# A5000_8MB_Glue.net
KiCad netlist of a schematic drawn in Altium Designer
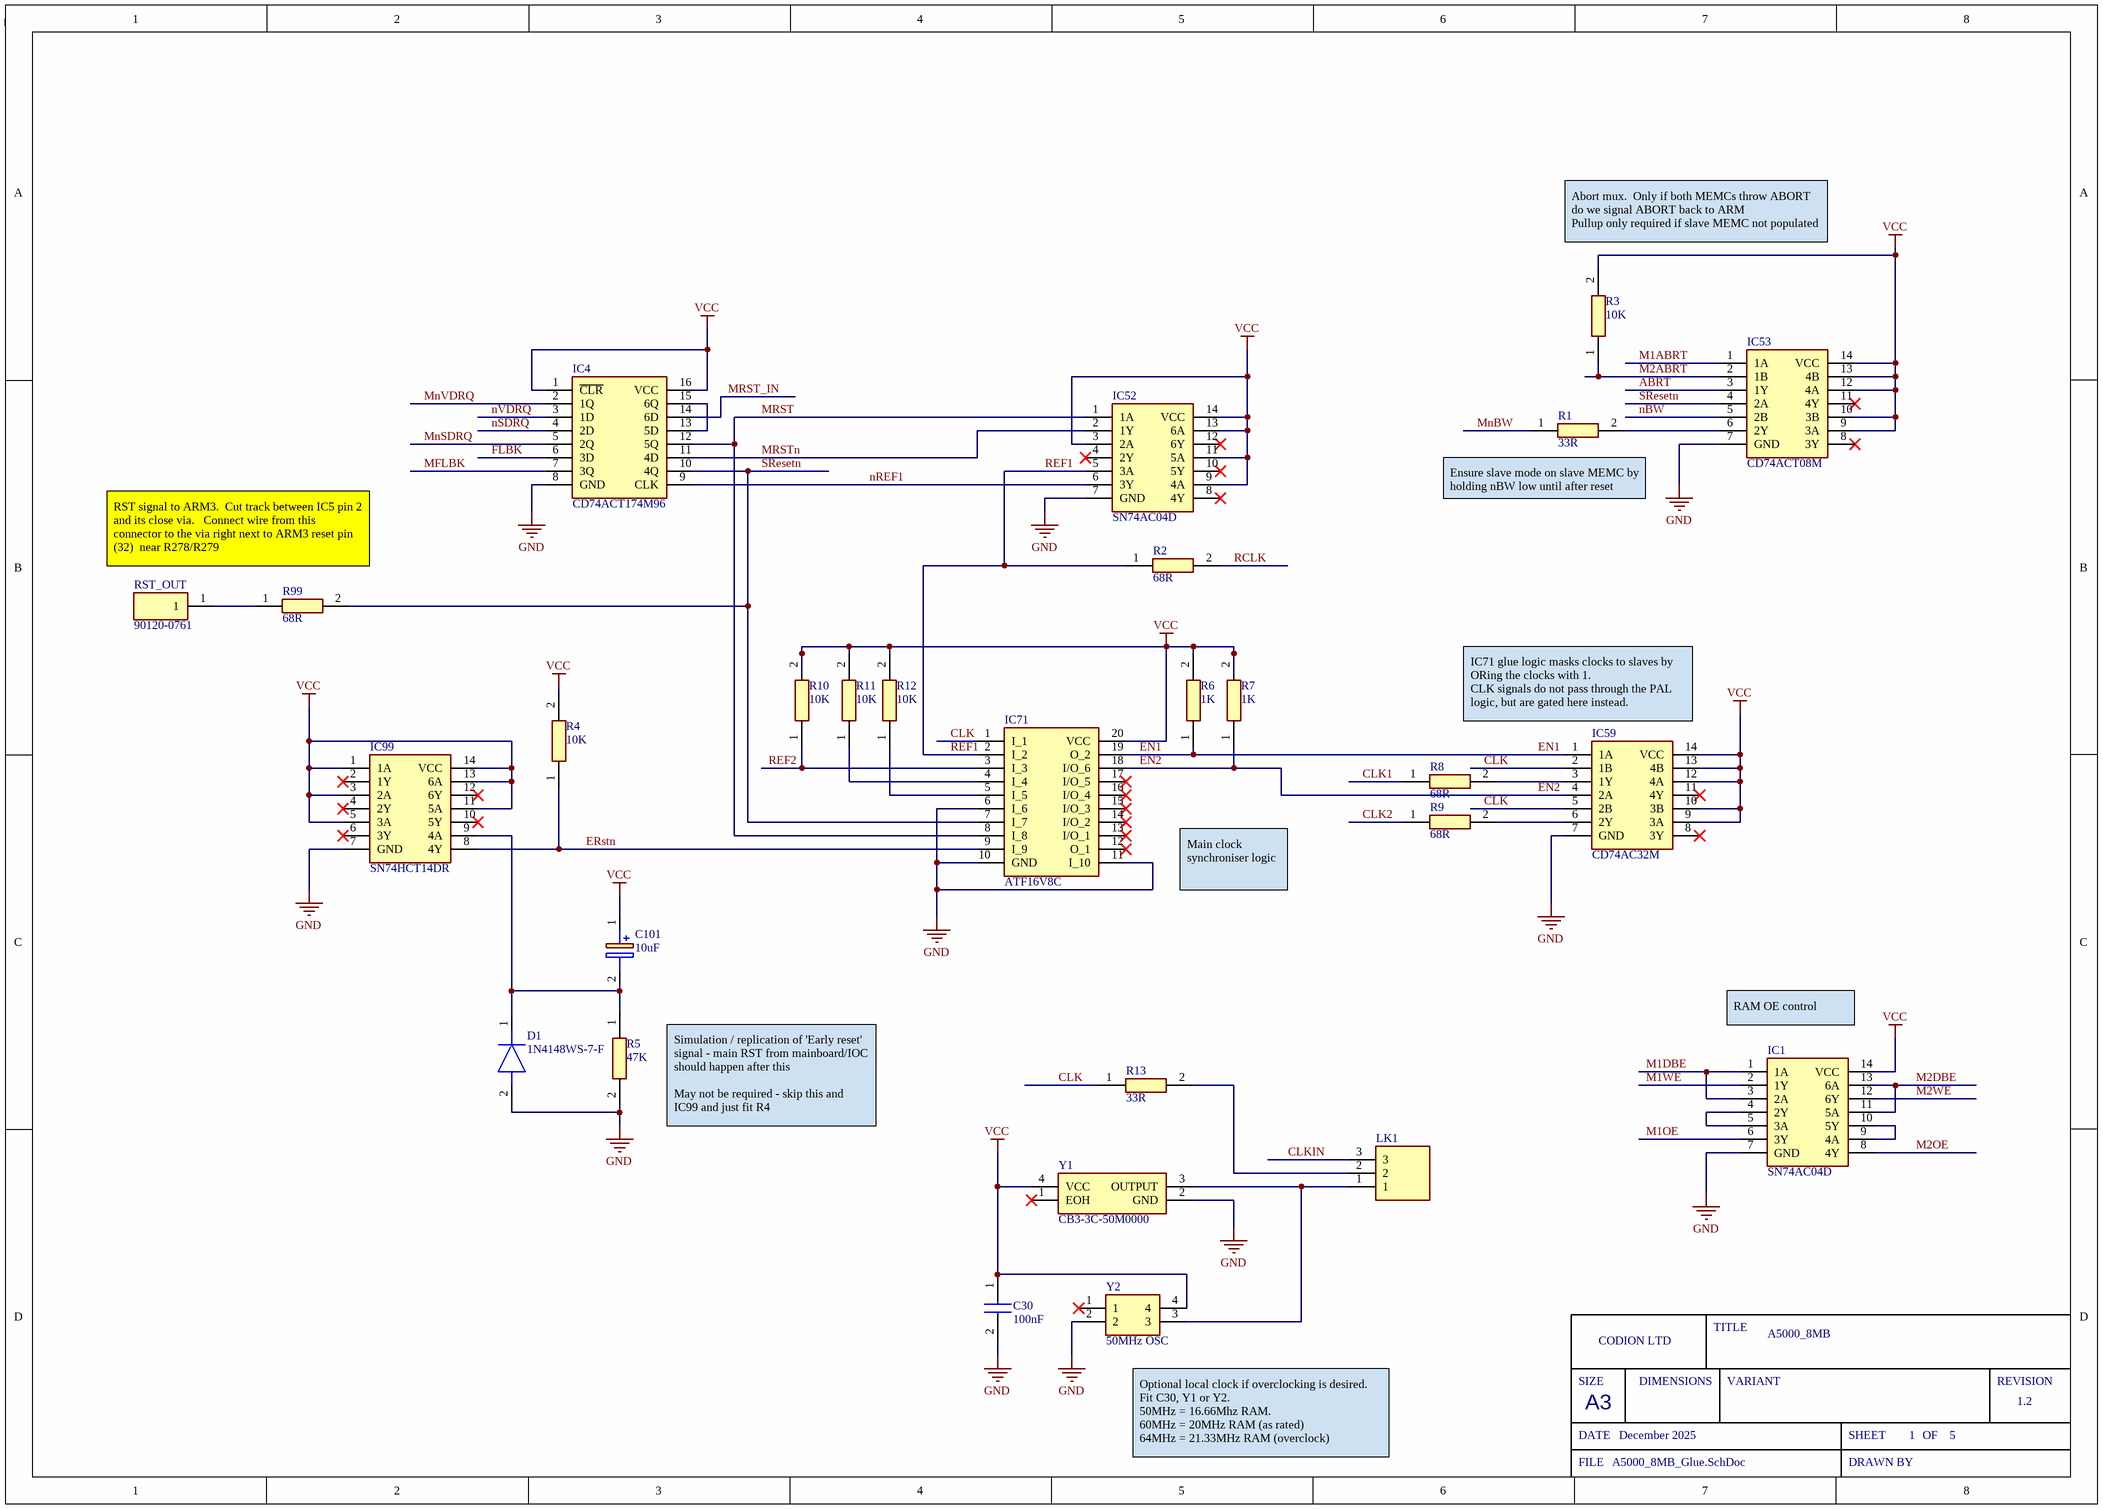
[diagram p0: A5000_8MB_Glue.SchDoc]

(export (version "E")
  (design (tool "Eeschema 10.0.6"))
  (components
    (comp (ref "C30")
      (value "100nF")
      (footprint "0805cap")
      (description "Capacitor")
      (fields
        (field (name "MANUFACTURER_PART_NUMBER") "C2012X7R1H104K125AM")
        (field (name "MOUSER PART NUMBER") "810-C2012X7R1H104KT5")
      )
      (libsource (lib "Acorn") (part "100nF0805"))
    )
    (comp (ref "C101")
      (value "10uF")
      (footprint "SamacSys:EEE0GA101SR")
      (description "Capacitor Polarised")
      (fields
        (field (name "MANUFACTURER_PART_NUMBER") "EEE-1EA100SR")
        (field (name "MOUSER PART NUMBER") "667-EEE-1EA100SR")
      )
      (libsource (lib "*") (part "EEE-1EA100SR"))
    )
    (comp (ref "D1")
      (value "1N4148WS-7-F")
      (footprint "SamacSys:SOD2513X120N")
      (description "Diode")
      (fields (field (name "MOUSER PART NUMBER") "621-1N4148WS-F") (field (name "LCSC PART #") "C2128"))
      (libsource (lib "SamacSys") (part "1N4148WS-7-F"))
    )
    (comp (ref "IC1")
      (value "SN74AC04D")
      (footprint "SamacSys:SOIC127P600X175-14N")
      (description "Integrated Circuit")
      (fields (field (name "MOUSER PART NUMBER") "595-SN74AC04D") (field (name "LCSC PART #") "C352940"))
      (libsource (lib "SamacSys") (part "SN74AC04D"))
    )
    (comp (ref "IC4")
      (value "CD74ACT174M96")
      (footprint "SamacSys:SOIC127P600X175-16N")
      (description "Integrated Circuit")
      (fields (field (name "MOUSER PART NUMBER") "595-CD74ACT174M96"))
      (libsource (lib "*") (part "CD74ACT174M96"))
    )
    (comp (ref "IC52")
      (value "SN74AC04D")
      (footprint "SamacSys:SOIC127P600X175-14N")
      (description "Integrated Circuit")
      (fields (field (name "MOUSER PART NUMBER") "595-SN74AC04D") (field (name "LCSC PART #") "C352940"))
      (libsource (lib "SamacSys") (part "SN74AC04D"))
    )
    (comp (ref "IC53")
      (value "CD74ACT08M")
      (footprint "SamacSys:SOIC127P600X175-14N")
      (description "Integrated Circuit")
      (fields (field (name "MOUSER PART NUMBER") "595-CD74ACT08M") (field (name "LCSC PART #") "C233452"))
      (libsource (lib "*") (part "CD74ACT08M"))
    )
    (comp (ref "IC59")
      (value "CD74AC32M")
      (footprint "SamacSys:SOIC127P600X175-14N")
      (description "Integrated Circuit")
      (fields (field (name "MOUSER PART NUMBER") "595-CD74AC32M") (field (name "LCSC PART #") "C352943"))
      (libsource (lib "SamacSys") (part "CD74AC32M"))
    )
    (comp (ref "IC71")
      (value "ATF16V8C")
      (footprint "SamacSys:DIP762W66P254L2692H508Q20N")
      (description "Integrated Circuit")
      (fields
        (field (name "MANUFACTURER_PART_NUMBER") "PAL16R4AMJ")
        (field (name "MOUSER PART NUMBER") "595-PAL16R4AMJ")
      )
      (libsource (lib "*") (part "PAL16R4AMJ"))
    )
    (comp (ref "IC99")
      (value "SN74HCT14DR")
      (footprint "SamacSys:SOIC127P600X175-14N")
      (description "Integrated Circuit")
      (fields (field (name "MOUSER PART NUMBER") "595-SN74HCT14DR") (field (name "LCSC PART #") "C6769"))
      (libsource (lib "SamacSys") (part "SN74HCT14DR"))
    )
    (comp (ref "LK1")
      (value "PREC003SAAN-RC")
      (footprint "SamacSys:HDRV3W64P0X254_1X3_762X254X868P")
      (description "Connector")
      (libsource (lib "SamacSys") (part "PREC003SAAN-RC"))
    )
    (comp (ref "R1")
      (value "33R")
      (footprint "SamacSys:RESC1005X40N")
      (description "Resistor")
      (fields
        (field (name "MANUFACTURER_PART_NUMBER") "CRCW040233R0FKED")
        (field (name "MOUSER PART NUMBER") "71-CRCW0402-33-E3")
      )
      (libsource (lib "SamacSys") (part "CRCW040233R0FKED"))
    )
    (comp (ref "R2")
      (value "68R")
      (footprint "SamacSys:RESC1005X40N")
      (description "Resistor")
      (fields
        (field (name "MANUFACTURER_PART_NUMBER") "CRCW040268R0FKEDHP")
        (field (name "MOUSER PART NUMBER") "71-CRCW040268R0FKEDH")
      )
      (libsource (lib "SamacSys") (part "CRCW040268R0FKEDHP"))
    )
    (comp (ref "R3")
      (value "10K")
      (footprint "SamacSys:RESC1005X40N")
      (description "Resistor")
      (fields
        (field (name "MANUFACTURER_PART_NUMBER") "CRCW040210K0FKEDHP")
        (field (name "MOUSER PART NUMBER") "71-CRCW040210K0FKEDH")
      )
      (libsource (lib "SamacSys") (part "CRCW040210K0FKEDHP"))
    )
    (comp (ref "R4")
      (value "10K")
      (footprint "SamacSys:RESC1005X40N")
      (description "Resistor")
      (fields
        (field (name "MANUFACTURER_PART_NUMBER") "CRCW040210K0FKEDHP")
        (field (name "MOUSER PART NUMBER") "71-CRCW040210K0FKEDH")
      )
      (libsource (lib "SamacSys") (part "CRCW040210K0FKEDHP"))
    )
    (comp (ref "R5")
      (value "47K")
      (footprint "SamacSys:RESC1005X40N")
      (description "Resistor")
      (fields
        (field (name "MANUFACTURER_PART_NUMBER") "CRCW040247K0FKED")
        (field (name "MOUSER PART NUMBER") "71-CRCW0402-47K-E3")
      )
      (libsource (lib "SamacSys") (part "CRCW040247K0FKED"))
    )
    (comp (ref "R6")
      (value "1K")
      (footprint "SamacSys:RESC1005X40N")
      (description "Resistor")
      (fields
        (field (name "MANUFACTURER_PART_NUMBER") "CRCW04021K00JNED")
        (field (name "MOUSER PART NUMBER") "71-CRCW0402J-1.0K-E3")
      )
      (libsource (lib "SamacSys") (part "CRCW04021K00JNED"))
    )
    (comp (ref "R7")
      (value "1K")
      (footprint "SamacSys:RESC1005X40N")
      (description "Resistor")
      (fields
        (field (name "MANUFACTURER_PART_NUMBER") "CRCW04021K00JNED")
        (field (name "MOUSER PART NUMBER") "71-CRCW0402J-1.0K-E3")
      )
      (libsource (lib "SamacSys") (part "CRCW04021K00JNED"))
    )
    (comp (ref "R8")
      (value "68R")
      (footprint "SamacSys:RESC1005X40N")
      (description "Resistor")
      (fields
        (field (name "MANUFACTURER_PART_NUMBER") "CRCW040268R0FKEDHP")
        (field (name "MOUSER PART NUMBER") "71-CRCW040268R0FKEDH")
      )
      (libsource (lib "SamacSys") (part "CRCW040268R0FKEDHP"))
    )
    (comp (ref "R9")
      (value "68R")
      (footprint "SamacSys:RESC1005X40N")
      (description "Resistor")
      (fields
        (field (name "MANUFACTURER_PART_NUMBER") "CRCW040268R0FKEDHP")
        (field (name "MOUSER PART NUMBER") "71-CRCW040268R0FKEDH")
      )
      (libsource (lib "SamacSys") (part "CRCW040268R0FKEDHP"))
    )
    (comp (ref "R10")
      (value "10K")
      (footprint "SamacSys:RESC1005X40N")
      (description "Resistor")
      (fields
        (field (name "MANUFACTURER_PART_NUMBER") "CRCW040210K0FKEDHP")
        (field (name "MOUSER PART NUMBER") "71-CRCW040210K0FKEDH")
      )
      (libsource (lib "SamacSys") (part "CRCW040210K0FKEDHP"))
    )
    (comp (ref "R11")
      (value "10K")
      (footprint "SamacSys:RESC1005X40N")
      (description "Resistor")
      (fields
        (field (name "MANUFACTURER_PART_NUMBER") "CRCW040210K0FKEDHP")
        (field (name "MOUSER PART NUMBER") "71-CRCW040210K0FKEDH")
      )
      (libsource (lib "SamacSys") (part "CRCW040210K0FKEDHP"))
    )
    (comp (ref "R12")
      (value "10K")
      (footprint "SamacSys:RESC1005X40N")
      (description "Resistor")
      (fields
        (field (name "MANUFACTURER_PART_NUMBER") "CRCW040210K0FKEDHP")
        (field (name "MOUSER PART NUMBER") "71-CRCW040210K0FKEDH")
      )
      (libsource (lib "SamacSys") (part "CRCW040210K0FKEDHP"))
    )
    (comp (ref "R13")
      (value "33R")
      (footprint "SamacSys:RESC1005X40N")
      (description "Resistor")
      (fields
        (field (name "MANUFACTURER_PART_NUMBER") "CRCW040233R0FKED")
        (field (name "MOUSER PART NUMBER") "71-CRCW0402-33-E3")
      )
      (libsource (lib "SamacSys") (part "CRCW040233R0FKED"))
    )
    (comp (ref "R99")
      (value "68R")
      (footprint "SamacSys:RESC1005X40N")
      (description "Resistor")
      (fields
        (field (name "MANUFACTURER_PART_NUMBER") "CRCW040268R0FKEDHP")
        (field (name "MOUSER PART NUMBER") "71-CRCW040268R0FKEDH")
      )
      (libsource (lib "SamacSys") (part "CRCW040268R0FKEDHP"))
    )
    (comp (ref "RST_OUT")
      (value "90120-0761")
      (footprint "SamacSys:HDRV1W90P0X254_1X1_232X249X560P")
      (description "Connector")
      (fields (field (name "MOUSER PART NUMBER") "538-90120-0761"))
      (libsource (lib "SamacSys") (part "90120-0761"))
    )
    (comp (ref "Y1")
      (value "CB3-3C-50M0000")
      (footprint "SamacSys:CB33C50M0000")
      (description "Crystal or Oscillator")
      (fields (field (name "MOUSER PART NUMBER") "774-CB3-3C-50M0"))
      (libsource (lib "*") (part "CB3-3C-50M0000"))
    )
    (comp (ref "Y2")
      (value "50MHz OSC")
      (footprint "SamacSys:DIPS762W56P1524L1778H241Q4N")
      (fields
        (field (name "MANUFACTURER_PART_NUMBER") "1107741")
        (field (name "MOUSER PART NUMBER") "535-1107741")
      )
      (libsource (lib "*") (part "1107741"))
    )
  )
  (nets
    (net (code "1") (name "/ABRT") (class "Default")
      (node (ref "IC53") (pin "3") (pinfunction "1Y_3") (pintype "passive"))
    )
    (net (code "2") (name "/CLK") (class "Default")
      (node (ref "IC59") (pin "2") (pinfunction "1B_2") (pintype "passive"))
      (node (ref "IC59") (pin "5") (pinfunction "2B_5") (pintype "passive"))
      (node (ref "IC71") (pin "1") (pinfunction "I_1_1") (pintype "passive"))
      (node (ref "R13") (pin "1") (pinfunction "1_1") (pintype "passive"))
    )
    (net (code "3") (name "/CLK1") (class "Default")
      (node (ref "R8") (pin "1") (pinfunction "1_1") (pintype "passive"))
    )
    (net (code "4") (name "/CLK2") (class "Default")
      (node (ref "R9") (pin "1") (pinfunction "1_1") (pintype "passive"))
    )
    (net (code "5") (name "/CLKIN") (class "Default")
      (node (ref "LK1") (pin "3") (pinfunction "3_3") (pintype "passive"))
    )
    (net (code "6") (name "/EN1") (class "Default")
      (node (ref "IC59") (pin "1") (pinfunction "1A_1") (pintype "passive"))
      (node (ref "IC71") (pin "19") (pinfunction "O_2_19") (pintype "passive"))
      (node (ref "R6") (pin "1") (pinfunction "1_1") (pintype "passive"))
    )
    (net (code "7") (name "/EN2") (class "Default")
      (node (ref "IC59") (pin "4") (pinfunction "2A_4") (pintype "passive"))
      (node (ref "IC71") (pin "18") (pinfunction "I/O_6_18") (pintype "passive"))
      (node (ref "R7") (pin "1") (pinfunction "1_1") (pintype "passive"))
    )
    (net (code "8") (name "/ERstn") (class "Default")
      (node (ref "IC71") (pin "9") (pinfunction "I_9_9") (pintype "passive"))
      (node (ref "IC99") (pin "8") (pinfunction "4Y_8") (pintype "passive"))
      (node (ref "R4") (pin "1") (pinfunction "1_1") (pintype "passive"))
    )
    (net (code "9") (name "/FLBK") (class "Default")
      (node (ref "IC4") (pin "6") (pinfunction "3D_6") (pintype "passive"))
    )
    (net (code "10") (name "/M1ABRT") (class "Default")
      (node (ref "IC53") (pin "1") (pinfunction "1A_1") (pintype "passive"))
    )
    (net (code "11") (name "/M1DBE") (class "Default")
      (node (ref "IC1") (pin "1") (pinfunction "1A_1") (pintype "passive"))
      (node (ref "IC1") (pin "3") (pinfunction "2A_3") (pintype "passive"))
    )
    (net (code "12") (name "/M1OE") (class "Default")
      (node (ref "IC1") (pin "6") (pinfunction "3Y_6") (pintype "passive"))
    )
    (net (code "13") (name "/M1WE") (class "Default")
      (node (ref "IC1") (pin "2") (pinfunction "1Y_2") (pintype "passive"))
    )
    (net (code "14") (name "/M2ABRT") (class "Default")
      (node (ref "IC53") (pin "2") (pinfunction "1B_2") (pintype "passive"))
      (node (ref "R3") (pin "1") (pinfunction "1_1") (pintype "passive"))
    )
    (net (code "15") (name "/M2DBE") (class "Default")
      (node (ref "IC1") (pin "11") (pinfunction "5A_11") (pintype "passive"))
      (node (ref "IC1") (pin "13") (pinfunction "6A_13") (pintype "passive"))
    )
    (net (code "16") (name "/M2OE") (class "Default")
      (node (ref "IC1") (pin "8") (pinfunction "4Y_8") (pintype "passive"))
    )
    (net (code "17") (name "/M2WE") (class "Default")
      (node (ref "IC1") (pin "12") (pinfunction "6Y_12") (pintype "passive"))
    )
    (net (code "18") (name "/MFLBK") (class "Default")
      (node (ref "IC4") (pin "7") (pinfunction "3Q_7") (pintype "passive"))
    )
    (net (code "19") (name "/MRST") (class "Default")
      (node (ref "IC4") (pin "12") (pinfunction "5Q_12") (pintype "passive"))
      (node (ref "IC52") (pin "1") (pinfunction "1A_1") (pintype "passive"))
      (node (ref "IC71") (pin "8") (pinfunction "I_8_8") (pintype "passive"))
    )
    (net (code "20") (name "/MRST_IN") (class "Default")
      (node (ref "IC4") (pin "14") (pinfunction "6D_14") (pintype "passive"))
    )
    (net (code "21") (name "/MRSTn") (class "Default")
      (node (ref "IC4") (pin "11") (pinfunction "4D_11") (pintype "passive"))
      (node (ref "IC52") (pin "2") (pinfunction "1Y_2") (pintype "passive"))
    )
    (net (code "22") (name "/MnBW") (class "Default")
      (node (ref "R1") (pin "1") (pinfunction "1_1") (pintype "passive"))
    )
    (net (code "23") (name "/MnSDRQ") (class "Default")
      (node (ref "IC4") (pin "5") (pinfunction "2Q_5") (pintype "passive"))
    )
    (net (code "24") (name "/MnVDRQ") (class "Default")
      (node (ref "IC4") (pin "2") (pinfunction "1Q_2") (pintype "passive"))
    )
    (net (code "25") (name "/RCLK") (class "Default")
      (node (ref "R2") (pin "2") (pinfunction "2_2") (pintype "passive"))
    )
    (net (code "26") (name "/REF1") (class "Default")
      (node (ref "IC52") (pin "5") (pinfunction "3A_5") (pintype "passive"))
      (node (ref "IC71") (pin "2") (pinfunction "I_2_2") (pintype "passive"))
      (node (ref "R2") (pin "1") (pinfunction "1_1") (pintype "passive"))
    )
    (net (code "27") (name "/REF2") (class "Default")
      (node (ref "IC71") (pin "3") (pinfunction "I_3_3") (pintype "passive"))
      (node (ref "R10") (pin "1") (pinfunction "1_1") (pintype "passive"))
    )
    (net (code "28") (name "/SResetn") (class "Default")
      (node (ref "IC4") (pin "10") (pinfunction "4Q_10") (pintype "passive"))
      (node (ref "IC53") (pin "4") (pinfunction "2A_4") (pintype "passive"))
      (node (ref "IC71") (pin "7") (pinfunction "I_7_7") (pintype "passive"))
      (node (ref "R99") (pin "2") (pinfunction "2_2") (pintype "passive"))
    )
    (net (code "29") (name "/nBW") (class "Default")
      (node (ref "IC53") (pin "5") (pinfunction "2B_5") (pintype "passive"))
    )
    (net (code "30") (name "/nREF1") (class "Default")
      (node (ref "IC4") (pin "9") (pinfunction "CLK_9") (pintype "passive"))
      (node (ref "IC52") (pin "6") (pinfunction "3Y_6") (pintype "passive"))
    )
    (net (code "31") (name "/nSDRQ") (class "Default")
      (node (ref "IC4") (pin "4") (pinfunction "2D_4") (pintype "passive"))
    )
    (net (code "32") (name "/nVDRQ") (class "Default")
      (node (ref "IC4") (pin "3") (pinfunction "1D_3") (pintype "passive"))
    )
    (net (code "33") (name "GND") (class "Default")
      (node (ref "C30") (pin "2") (pinfunction "2_2") (pintype "passive"))
      (node (ref "D1") (pin "2") (pinfunction "A_2") (pintype "passive"))
      (node (ref "IC1") (pin "7") (pinfunction "GND_7") (pintype "passive"))
      (node (ref "IC4") (pin "8") (pinfunction "GND_8") (pintype "passive"))
      (node (ref "IC52") (pin "7") (pinfunction "GND_7") (pintype "passive"))
      (node (ref "IC53") (pin "7") (pinfunction "GND_7") (pintype "passive"))
      (node (ref "IC59") (pin "7") (pinfunction "GND_7") (pintype "passive"))
      (node (ref "IC71") (pin "10") (pinfunction "GND_10") (pintype "passive"))
      (node (ref "IC71") (pin "11") (pinfunction "I_10_11") (pintype "passive"))
      (node (ref "IC71") (pin "6") (pinfunction "I_6_6") (pintype "passive"))
      (node (ref "IC99") (pin "7") (pinfunction "GND_7") (pintype "passive"))
      (node (ref "R5") (pin "2") (pinfunction "2_2") (pintype "passive"))
      (node (ref "Y1") (pin "2") (pinfunction "GND_2") (pintype "passive"))
      (node (ref "Y2") (pin "2") (pinfunction "2_2") (pintype "passive"))
    )
    (net (code "34") (name "Net-(C101--)") (class "Default")
      (node (ref "C101") (pin "2") (pinfunction "-_2") (pintype "passive"))
      (node (ref "D1") (pin "1") (pinfunction "K_1") (pintype "passive"))
      (node (ref "IC99") (pin "9") (pinfunction "4A_9") (pintype "passive"))
      (node (ref "R5") (pin "1") (pinfunction "1_1") (pintype "passive"))
    )
    (net (code "35") (name "Net-(IC1-2Y)") (class "Default")
      (node (ref "IC1") (pin "4") (pinfunction "2Y_4") (pintype "passive"))
      (node (ref "IC1") (pin "5") (pinfunction "3A_5") (pintype "passive"))
    )
    (net (code "36") (name "Net-(IC1-4A)") (class "Default")
      (node (ref "IC1") (pin "10") (pinfunction "5Y_10") (pintype "passive"))
      (node (ref "IC1") (pin "9") (pinfunction "4A_9") (pintype "passive"))
    )
    (net (code "37") (name "Net-(IC4-5D)") (class "Default")
      (node (ref "IC4") (pin "13") (pinfunction "5D_13") (pintype "passive"))
      (node (ref "IC4") (pin "15") (pinfunction "6Q_15") (pintype "passive"))
    )
    (net (code "38") (name "Net-(IC53-2Y)") (class "Default")
      (node (ref "IC53") (pin "6") (pinfunction "2Y_6") (pintype "passive"))
      (node (ref "R1") (pin "2") (pinfunction "2_2") (pintype "passive"))
    )
    (net (code "39") (name "Net-(IC59-1Y)") (class "Default")
      (node (ref "IC59") (pin "3") (pinfunction "1Y_3") (pintype "passive"))
      (node (ref "R8") (pin "2") (pinfunction "2_2") (pintype "passive"))
    )
    (net (code "40") (name "Net-(IC59-2Y)") (class "Default")
      (node (ref "IC59") (pin "6") (pinfunction "2Y_6") (pintype "passive"))
      (node (ref "R9") (pin "2") (pinfunction "2_2") (pintype "passive"))
    )
    (net (code "41") (name "Net-(IC71-I_4)") (class "Default")
      (node (ref "IC71") (pin "4") (pinfunction "I_4_4") (pintype "passive"))
      (node (ref "R11") (pin "1") (pinfunction "1_1") (pintype "passive"))
    )
    (net (code "42") (name "Net-(IC71-I_5)") (class "Default")
      (node (ref "IC71") (pin "5") (pinfunction "I_5_5") (pintype "passive"))
      (node (ref "R12") (pin "1") (pinfunction "1_1") (pintype "passive"))
    )
    (net (code "43") (name "Net-(LK1-Pad2)") (class "Default")
      (node (ref "LK1") (pin "2") (pinfunction "2_2") (pintype "passive"))
      (node (ref "R13") (pin "2") (pinfunction "2_2") (pintype "passive"))
    )
    (net (code "44") (name "Net-(R99-Pad1)") (class "Default")
      (node (ref "R99") (pin "1") (pinfunction "1_1") (pintype "passive"))
      (node (ref "RST_OUT") (pin "1") (pinfunction "1_1") (pintype "passive"))
    )
    (net (code "45") (name "Net-(Y1-OUTPUT)") (class "Default")
      (node (ref "LK1") (pin "1") (pinfunction "1_1") (pintype "passive"))
      (node (ref "Y1") (pin "3") (pinfunction "OUTPUT_3") (pintype "passive"))
      (node (ref "Y2") (pin "3") (pinfunction "3_3") (pintype "passive"))
    )
    (net (code "46") (name "VCC") (class "Default")
      (node (ref "C101") (pin "1") (pinfunction "+_1") (pintype "passive"))
      (node (ref "C30") (pin "1") (pinfunction "1_1") (pintype "passive"))
      (node (ref "IC1") (pin "14") (pinfunction "VCC_14") (pintype "passive"))
      (node (ref "IC4") (pin "1") (pinfunction "~{CLR}_1") (pintype "passive"))
      (node (ref "IC4") (pin "16") (pinfunction "VCC_16") (pintype "passive"))
      (node (ref "IC52") (pin "11") (pinfunction "5A_11") (pintype "passive"))
      (node (ref "IC52") (pin "13") (pinfunction "6A_13") (pintype "passive"))
      (node (ref "IC52") (pin "14") (pinfunction "VCC_14") (pintype "passive"))
      (node (ref "IC52") (pin "3") (pinfunction "2A_3") (pintype "passive"))
      (node (ref "IC52") (pin "9") (pinfunction "4A_9") (pintype "passive"))
      (node (ref "IC53") (pin "10") (pinfunction "3B_10") (pintype "passive"))
      (node (ref "IC53") (pin "12") (pinfunction "4A_12") (pintype "passive"))
      (node (ref "IC53") (pin "13") (pinfunction "4B_13") (pintype "passive"))
      (node (ref "IC53") (pin "14") (pinfunction "VCC_14") (pintype "passive"))
      (node (ref "IC53") (pin "9") (pinfunction "3A_9") (pintype "passive"))
      (node (ref "IC59") (pin "10") (pinfunction "3B_10") (pintype "passive"))
      (node (ref "IC59") (pin "12") (pinfunction "4A_12") (pintype "passive"))
      (node (ref "IC59") (pin "13") (pinfunction "4B_13") (pintype "passive"))
      (node (ref "IC59") (pin "14") (pinfunction "VCC_14") (pintype "passive"))
      (node (ref "IC59") (pin "9") (pinfunction "3A_9") (pintype "passive"))
      (node (ref "IC71") (pin "20") (pinfunction "VCC_20") (pintype "passive"))
      (node (ref "IC99") (pin "1") (pinfunction "1A_1") (pintype "passive"))
      (node (ref "IC99") (pin "11") (pinfunction "5A_11") (pintype "passive"))
      (node (ref "IC99") (pin "13") (pinfunction "6A_13") (pintype "passive"))
      (node (ref "IC99") (pin "14") (pinfunction "VCC_14") (pintype "passive"))
      (node (ref "IC99") (pin "3") (pinfunction "2A_3") (pintype "passive"))
      (node (ref "IC99") (pin "5") (pinfunction "3A_5") (pintype "passive"))
      (node (ref "R10") (pin "2") (pinfunction "2_2") (pintype "passive"))
      (node (ref "R11") (pin "2") (pinfunction "2_2") (pintype "passive"))
      (node (ref "R12") (pin "2") (pinfunction "2_2") (pintype "passive"))
      (node (ref "R3") (pin "2") (pinfunction "2_2") (pintype "passive"))
      (node (ref "R4") (pin "2") (pinfunction "2_2") (pintype "passive"))
      (node (ref "R6") (pin "2") (pinfunction "2_2") (pintype "passive"))
      (node (ref "R7") (pin "2") (pinfunction "2_2") (pintype "passive"))
      (node (ref "Y1") (pin "4") (pinfunction "VCC_4") (pintype "passive"))
      (node (ref "Y2") (pin "4") (pinfunction "4_4") (pintype "passive"))
    )
    (net (code "47") (name "unconnected-(IC52-2Y-Pad4)") (class "Default")
      (node (ref "IC52") (pin "4") (pinfunction "2Y_4") (pintype "passive+no_connect"))
    )
    (net (code "48") (name "unconnected-(IC52-4Y-Pad8)") (class "Default")
      (node (ref "IC52") (pin "8") (pinfunction "4Y_8") (pintype "passive+no_connect"))
    )
    (net (code "49") (name "unconnected-(IC52-5Y-Pad10)") (class "Default")
      (node (ref "IC52") (pin "10") (pinfunction "5Y_10") (pintype "passive+no_connect"))
    )
    (net (code "50") (name "unconnected-(IC52-6Y-Pad12)") (class "Default")
      (node (ref "IC52") (pin "12") (pinfunction "6Y_12") (pintype "passive+no_connect"))
    )
    (net (code "51") (name "unconnected-(IC53-3Y-Pad8)") (class "Default")
      (node (ref "IC53") (pin "8") (pinfunction "3Y_8") (pintype "passive+no_connect"))
    )
    (net (code "52") (name "unconnected-(IC53-4Y-Pad11)") (class "Default")
      (node (ref "IC53") (pin "11") (pinfunction "4Y_11") (pintype "passive+no_connect"))
    )
    (net (code "53") (name "unconnected-(IC59-3Y-Pad8)") (class "Default")
      (node (ref "IC59") (pin "8") (pinfunction "3Y_8") (pintype "passive+no_connect"))
    )
    (net (code "54") (name "unconnected-(IC59-4Y-Pad11)") (class "Default")
      (node (ref "IC59") (pin "11") (pinfunction "4Y_11") (pintype "passive+no_connect"))
    )
    (net (code "55") (name "unconnected-(IC71-I{slash}O_1-Pad13)") (class "Default")
      (node (ref "IC71") (pin "13") (pinfunction "I/O_1_13") (pintype "passive+no_connect"))
    )
    (net (code "56") (name "unconnected-(IC71-I{slash}O_2-Pad14)") (class "Default")
      (node (ref "IC71") (pin "14") (pinfunction "I/O_2_14") (pintype "passive+no_connect"))
    )
    (net (code "57") (name "unconnected-(IC71-I{slash}O_3-Pad15)") (class "Default")
      (node (ref "IC71") (pin "15") (pinfunction "I/O_3_15") (pintype "passive+no_connect"))
    )
    (net (code "58") (name "unconnected-(IC71-I{slash}O_4-Pad16)") (class "Default")
      (node (ref "IC71") (pin "16") (pinfunction "I/O_4_16") (pintype "passive+no_connect"))
    )
    (net (code "59") (name "unconnected-(IC71-I{slash}O_5-Pad17)") (class "Default")
      (node (ref "IC71") (pin "17") (pinfunction "I/O_5_17") (pintype "passive+no_connect"))
    )
    (net (code "60") (name "unconnected-(IC71-O_1-Pad12)") (class "Default")
      (node (ref "IC71") (pin "12") (pinfunction "O_1_12") (pintype "passive+no_connect"))
    )
    (net (code "61") (name "unconnected-(IC99-1Y-Pad2)") (class "Default")
      (node (ref "IC99") (pin "2") (pinfunction "1Y_2") (pintype "passive+no_connect"))
    )
    (net (code "62") (name "unconnected-(IC99-2Y-Pad4)") (class "Default")
      (node (ref "IC99") (pin "4") (pinfunction "2Y_4") (pintype "passive+no_connect"))
    )
    (net (code "63") (name "unconnected-(IC99-3Y-Pad6)") (class "Default")
      (node (ref "IC99") (pin "6") (pinfunction "3Y_6") (pintype "passive+no_connect"))
    )
    (net (code "64") (name "unconnected-(IC99-5Y-Pad10)") (class "Default")
      (node (ref "IC99") (pin "10") (pinfunction "5Y_10") (pintype "passive+no_connect"))
    )
    (net (code "65") (name "unconnected-(IC99-6Y-Pad12)") (class "Default")
      (node (ref "IC99") (pin "12") (pinfunction "6Y_12") (pintype "passive+no_connect"))
    )
    (net (code "66") (name "unconnected-(Y1-EOH-Pad1)") (class "Default")
      (node (ref "Y1") (pin "1") (pinfunction "EOH_1") (pintype "passive+no_connect"))
    )
    (net (code "67") (name "unconnected-(Y2-Pad1)") (class "Default")
      (node (ref "Y2") (pin "1") (pinfunction "1_1") (pintype "passive+no_connect"))
    )
  )
)
